# Adjustable_PSU_-_TVHR-002.net
KiCad netlist of a schematic drawn in EAGLE
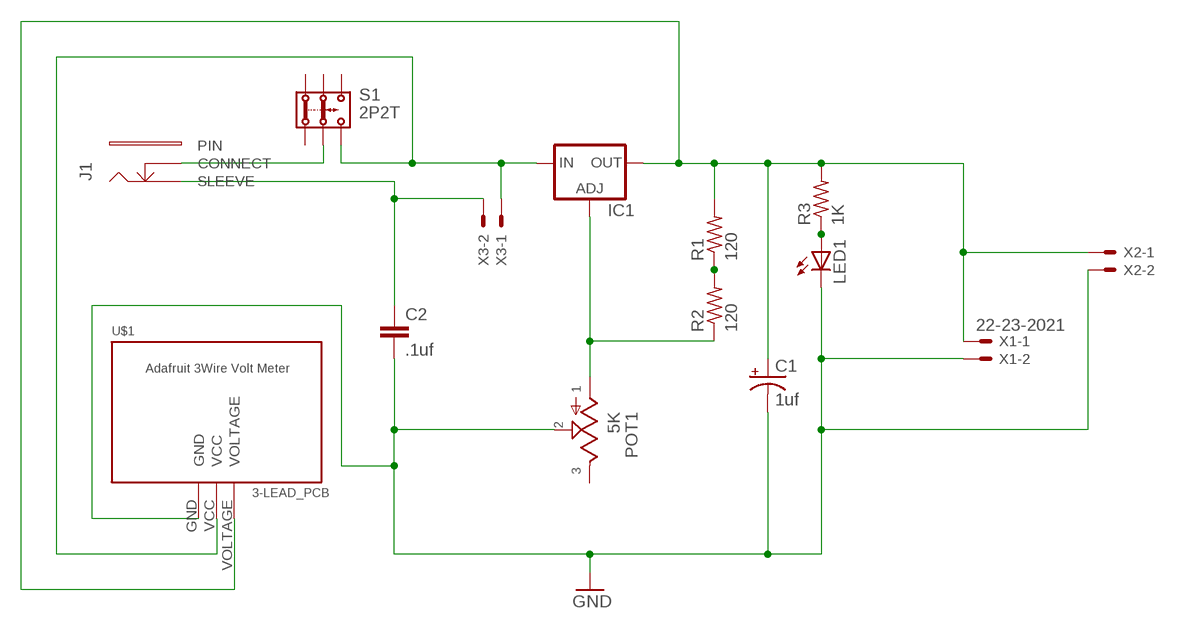
[diagram p0: schematic, sheet 1]

(export (version "E")
  (design (tool "Eeschema 10.0.6"))
  (components
    (comp (ref "C1")
      (value "1uf")
      (footprint "eagle-import:E2-5")
      (libsource (lib "eagle-import") (part "CPOL-USE2-5"))
    )
    (comp (ref "C2")
      (value ".1uf")
      (footprint "eagle-import:C025-030X050")
      (libsource (lib "eagle-import") (part "C-EU025-030X050"))
    )
    (comp (ref "IC1")
      (value "LM317TL")
      (footprint "eagle-import:317TL")
      (libsource (lib "eagle-import") (part "LM317TL"))
    )
    (comp (ref "J1")
      (value "DCBOSS")
      (footprint "eagle-import:BOSS_JACK")
      (libsource (lib "eagle-import") (part "DCBOSS"))
    )
    (comp (ref "LED1")
      (value "LED3MM")
      (footprint "eagle-import:LED3MM")
      (libsource (lib "eagle-import") (part "LED3MM"))
    )
    (comp (ref "POT1")
      (value "5K")
      (footprint "eagle-import:16MM")
      (libsource (lib "eagle-import") (part "POT16MM"))
    )
    (comp (ref "R1")
      (value "120")
      (footprint "eagle-import:0207_10")
      (libsource (lib "eagle-import") (part "R-US_0207/10"))
    )
    (comp (ref "R2")
      (value "120")
      (footprint "eagle-import:0207_10")
      (libsource (lib "eagle-import") (part "R-US_0207/10"))
    )
    (comp (ref "R3")
      (value "1K")
      (footprint "eagle-import:0207_10")
      (libsource (lib "eagle-import") (part "R-US_0207/10"))
    )
    (comp (ref "S1")
      (value "2P2T")
      (footprint "eagle-import:2P2T")
      (libsource (lib "eagle-import") (part "2P2T"))
    )
    (comp (ref "U$1")
      (value "3-LEAD_PCB")
      (footprint "eagle-import:3-LEAD_PCB")
      (libsource (lib "eagle-import") (part "3-LEAD_PCB"))
    )
    (comp (ref "X1")
      (value "22-23-2021")
      (footprint "eagle-import:22-23-2021")
      (fields (field (name "MF") "MOLEX"))
      (libsource (lib "eagle-import") (part "22-23-2021"))
    )
    (comp (ref "X2")
      (value "KK-156-2")
      (footprint "eagle-import:KK-156-2")
      (libsource (lib "eagle-import") (part "KK-156-2"))
    )
    (comp (ref "X3")
      (value "KK-156-2")
      (footprint "eagle-import:KK-156-2")
      (libsource (lib "eagle-import") (part "KK-156-2"))
    )
  )
  (nets
    (net (code "1") (name "GND") (class "Default")
      (node (ref "C1") (pin "-") (pinfunction "-_-") (pintype "passive"))
      (node (ref "C2") (pin "2") (pinfunction "2_2") (pintype "passive"))
      (node (ref "LED1") (pin "K") (pinfunction "C_K") (pintype "passive"))
      (node (ref "POT1") (pin "2") (pinfunction "2_2") (pintype "passive"))
      (node (ref "U$1") (pin "GND") (pinfunction "GND_GND") (pintype "bidirectional"))
      (node (ref "X1") (pin "2") (pinfunction "S_2") (pintype "passive"))
      (node (ref "X2") (pin "2") (pinfunction "S_2") (pintype "passive"))
    )
    (net (code "2") (name "Net-(IC1-ADJ)") (class "Default")
      (node (ref "IC1") (pin "1") (pinfunction "ADJ_1") (pintype "input"))
      (node (ref "POT1") (pin "1") (pinfunction "1_1") (pintype "passive"))
      (node (ref "R2") (pin "1") (pinfunction "1_1") (pintype "passive"))
    )
    (net (code "3") (name "Net-(IC1-IN)") (class "Default")
      (node (ref "IC1") (pin "3") (pinfunction "IN_3") (pintype "input"))
      (node (ref "S1") (pin "3.2") (pinfunction "3.2_3.2") (pintype "passive"))
      (node (ref "U$1") (pin "VCC") (pinfunction "VCC_VCC") (pintype "bidirectional"))
      (node (ref "X3") (pin "1") (pinfunction "S_1") (pintype "passive"))
    )
    (net (code "4") (name "Net-(IC1-OUT)") (class "Default")
      (node (ref "C1") (pin "+") (pinfunction "+_+") (pintype "passive"))
      (node (ref "IC1") (pin "2") (pinfunction "OUT_2") (pintype "passive"))
      (node (ref "R1") (pin "2") (pinfunction "2_2") (pintype "passive"))
      (node (ref "R3") (pin "2") (pinfunction "2_2") (pintype "passive"))
      (node (ref "U$1") (pin "VOLTAGE") (pinfunction "VOLTAGE_VOLTAGE") (pintype "bidirectional"))
      (node (ref "X1") (pin "1") (pinfunction "S_1") (pintype "passive"))
      (node (ref "X2") (pin "1") (pinfunction "S_1") (pintype "passive"))
    )
    (net (code "5") (name "Net-(J1-CONNECT)") (class "Default")
      (node (ref "J1") (pin "CLOSE") (pinfunction "CONNECT_CLOSE") (pintype "passive"))
      (node (ref "S1") (pin "2.2") (pinfunction "2.2_2.2") (pintype "passive"))
    )
    (net (code "6") (name "Net-(LED1-PadA)") (class "Default")
      (node (ref "LED1") (pin "A") (pinfunction "A_A") (pintype "passive"))
      (node (ref "R3") (pin "1") (pinfunction "1_1") (pintype "passive"))
    )
    (net (code "7") (name "Net-(R1-Pad1)") (class "Default")
      (node (ref "R1") (pin "1") (pinfunction "1_1") (pintype "passive"))
      (node (ref "R2") (pin "2") (pinfunction "2_2") (pintype "passive"))
    )
    (net (code "8") (name "Net-(X3B-S)") (class "Default")
      (node (ref "C2") (pin "1") (pinfunction "1_1") (pintype "passive"))
      (node (ref "J1") (pin "SLEEVE") (pinfunction "SLEEVE_SLEEVE") (pintype "passive"))
      (node (ref "X3") (pin "2") (pinfunction "S_2") (pintype "passive"))
    )
    (net (code "9") (name "unconnected-(J1-PadPIN)") (class "Default")
      (node (ref "J1") (pin "PIN") (pinfunction "PIN_PIN") (pintype "passive"))
    )
    (net (code "10") (name "unconnected-(POT1-Pad3)") (class "Default")
      (node (ref "POT1") (pin "3") (pinfunction "3_3") (pintype "passive"))
    )
    (net (code "11") (name "unconnected-(S1-Pad1.1)") (class "Default")
      (node (ref "S1") (pin "1.1") (pinfunction "1.1_1.1") (pintype "passive"))
    )
    (net (code "12") (name "unconnected-(S1-Pad1.2)") (class "Default")
      (node (ref "S1") (pin "1.2") (pinfunction "1.2_1.2") (pintype "passive"))
    )
    (net (code "13") (name "unconnected-(S1-Pad2.1)") (class "Default")
      (node (ref "S1") (pin "2.1") (pinfunction "2.1_2.1") (pintype "passive"))
    )
    (net (code "14") (name "unconnected-(S1-Pad3.1)") (class "Default")
      (node (ref "S1") (pin "3.1") (pinfunction "3.1_3.1") (pintype "passive"))
    )
  )
)
